# 4_MOTORES_DC.net
KiCad netlist of a schematic drawn in Altium Designer
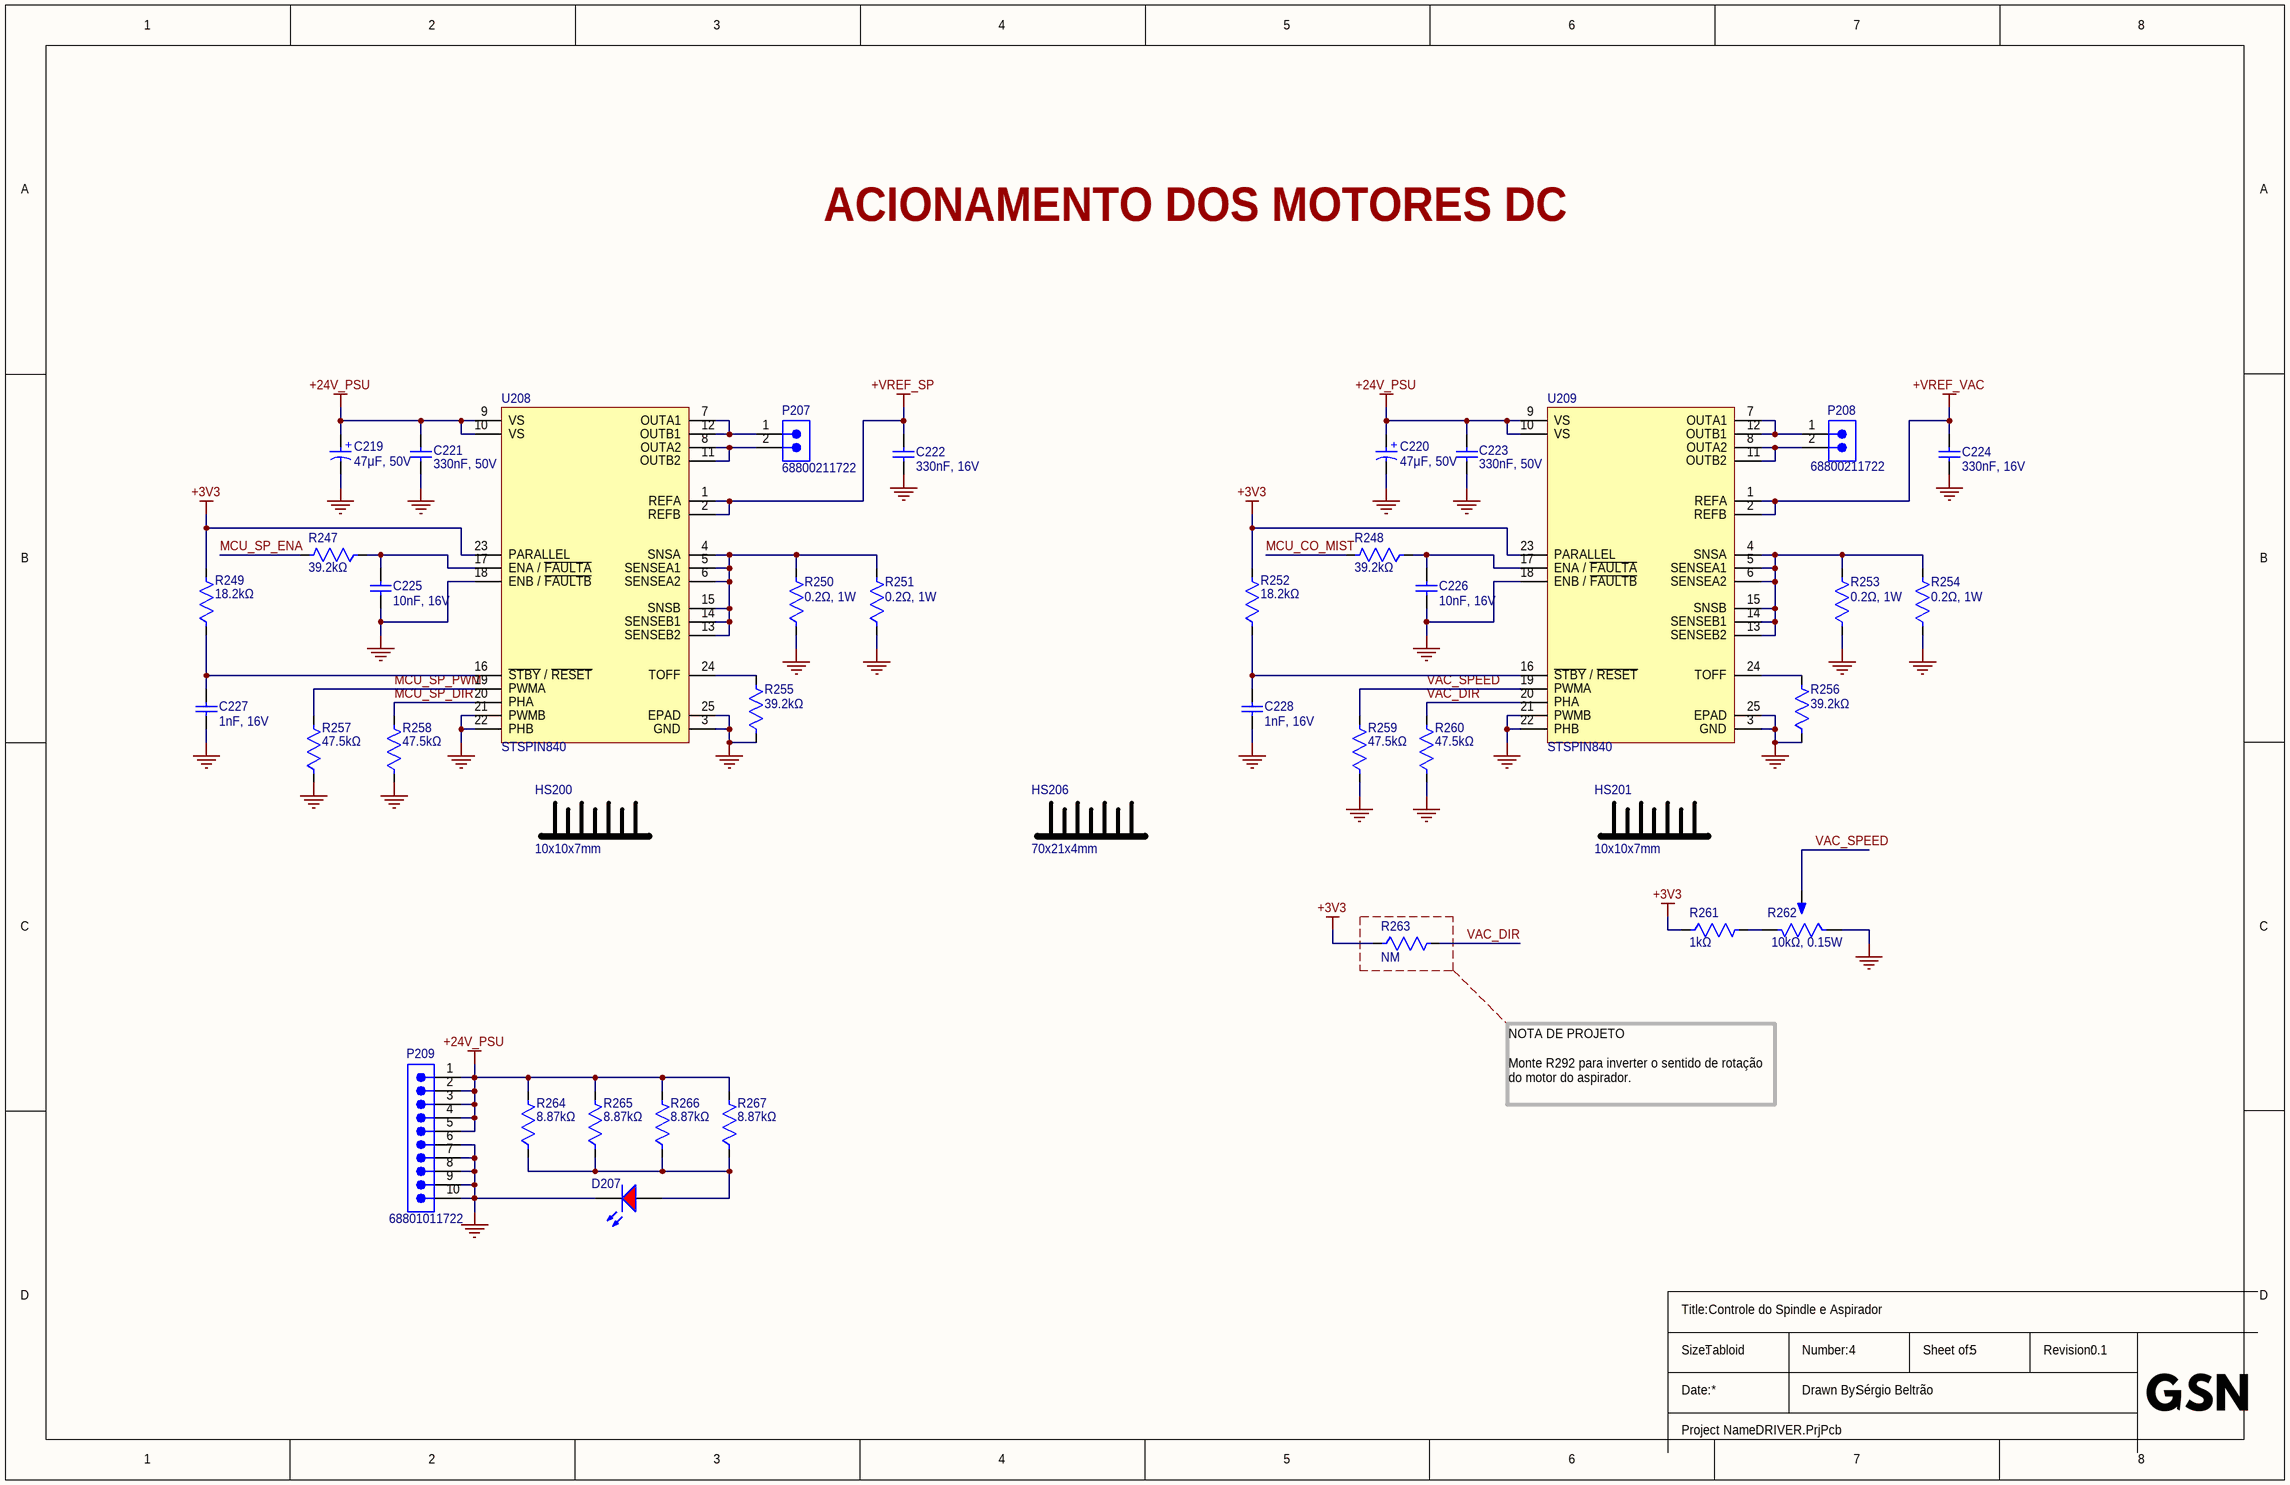
[diagram p0: 4_MOTORES_DC.SchDoc]

(export (version "E")
  (design (tool "Eeschema 10.0.6"))
  (components
    (comp (ref "C219")
      (value "47μF, 50V")
      (footprint "WCAP-ASLI_D6.3H7.7")
      (description "WCAP-ASLI Aluminum Electrolytic Capacitor, V-Chip, SMT, 6.3mm x 7.7mm, 47μF, 50V")
      (fields
        (field (name "MANUFACTURER PART NUMBER") "865080645012")
        (field (name "MANUFACTURER") "Wurth Elektronik")
      )
      (libsource (lib "WE - Passive Components") (part "Capacitor_Polarized"))
    )
    (comp (ref "C220")
      (value "47μF, 50V")
      (footprint "WCAP-ASLI_D6.3H7.7")
      (description "WCAP-ASLI Aluminum Electrolytic Capacitor, V-Chip, SMT, 6.3mm x 7.7mm, 47μF, 50V")
      (fields
        (field (name "MANUFACTURER PART NUMBER") "865080645012")
        (field (name "MANUFACTURER") "Wurth Elektronik")
      )
      (libsource (lib "WE - Passive Components") (part "Capacitor_Polarized"))
    )
    (comp (ref "C221")
      (value "330nF, 50V")
      (footprint "WCAP-CSGP_0603_L1.6W0.8H0.8_Wave")
      (description "WCAP-CSGP Multilayer Ceramic Chip Capacitor, General Purpose, size 0603, 330nF, 50V")
      (fields
        (field (name "MANUFACTURER PART NUMBER") "885012206121")
        (field (name "MANUFACTURER") "Wurth Elektronik")
      )
      (libsource (lib "WE - Passive Components") (part "Capacitor_Non-Polarized"))
    )
    (comp (ref "C222")
      (value "330nF, 16V")
      (footprint "WCAP-CSGP_0603_L1.6W0.8H0.8_Wave")
      (description "WCAP-CSGP Multilayer Ceramic Chip Capacitor, General Purpose, size 0603, 330nF, 16V")
      (fields
        (field (name "MANUFACTURER PART NUMBER") "885012206049")
        (field (name "MANUFACTURER") "Wurth Elektronik")
      )
      (libsource (lib "WE - Passive Components") (part "Capacitor_Non-Polarized"))
    )
    (comp (ref "C223")
      (value "330nF, 50V")
      (footprint "WCAP-CSGP_0603_L1.6W0.8H0.8_Wave")
      (description "WCAP-CSGP Multilayer Ceramic Chip Capacitor, General Purpose, size 0603, 330nF, 50V")
      (fields
        (field (name "MANUFACTURER PART NUMBER") "885012206121")
        (field (name "MANUFACTURER") "Wurth Elektronik")
      )
      (libsource (lib "WE - Passive Components") (part "Capacitor_Non-Polarized"))
    )
    (comp (ref "C224")
      (value "330nF, 16V")
      (footprint "WCAP-CSGP_0603_L1.6W0.8H0.8_Wave")
      (description "WCAP-CSGP Multilayer Ceramic Chip Capacitor, General Purpose, size 0603, 330nF, 16V")
      (fields
        (field (name "MANUFACTURER PART NUMBER") "885012206049")
        (field (name "MANUFACTURER") "Wurth Elektronik")
      )
      (libsource (lib "WE - Passive Components") (part "Capacitor_Non-Polarized"))
    )
    (comp (ref "C225")
      (value "10nF, 16V")
      (footprint "WCAP-CSGP_0603_L1.6W0.8H0.8_Wave")
      (description "WCAP-CSGP Multilayer Ceramic Chip Capacitor, General Purpose, size 0603, 10nF, 16V")
      (fields
        (field (name "MANUFACTURER PART NUMBER") "885012206040")
        (field (name "MANUFACTURER") "Wurth Elektronik")
      )
      (libsource (lib "WE - Passive Components") (part "Capacitor_Non-Polarized"))
    )
    (comp (ref "C226")
      (value "10nF, 16V")
      (footprint "WCAP-CSGP_0603_L1.6W0.8H0.8_Wave")
      (description "WCAP-CSGP Multilayer Ceramic Chip Capacitor, General Purpose, size 0603, 10nF, 16V")
      (fields
        (field (name "MANUFACTURER PART NUMBER") "885012206040")
        (field (name "MANUFACTURER") "Wurth Elektronik")
      )
      (libsource (lib "WE - Passive Components") (part "Capacitor_Non-Polarized"))
    )
    (comp (ref "C227")
      (value "1nF, 16V")
      (footprint "WCAP-CSGP_0603_L1.6W0.8H0.8_Wave")
      (description "WCAP-CSGP Multilayer Ceramic Chip Capacitor, General Purpose, size 0603, 1nF, 16V")
      (fields
        (field (name "MANUFACTURER PART NUMBER") "885012206034")
        (field (name "MANUFACTURER") "Wurth Elektronik")
      )
      (libsource (lib "WE - Passive Components") (part "Capacitor_Non-Polarized"))
    )
    (comp (ref "C228")
      (value "1nF, 16V")
      (footprint "WCAP-CSGP_0603_L1.6W0.8H0.8_Wave")
      (description "WCAP-CSGP Multilayer Ceramic Chip Capacitor, General Purpose, size 0603, 1nF, 16V")
      (fields
        (field (name "MANUFACTURER PART NUMBER") "885012206034")
        (field (name "MANUFACTURER") "Wurth Elektronik")
      )
      (libsource (lib "WE - Passive Components") (part "Capacitor_Non-Polarized"))
    )
    (comp (ref "D207")
      (value "Red, 2V, 140deg")
      (footprint "WL-SMCW_0603_150060xx75003")
      (description "WL-SMCW Mono-color Chip LED Waterclear, SMT, size 0603, Red, 2V, 140°")
      (fields
        (field (name "MANUFACTURER PART NUMBER") "150060RS75003")
        (field (name "MANUFACTURER") "Wurth Elektronik")
      )
      (libsource (lib "WE - Optoelectronic Components") (part "LED_Red_1A-2K"))
    )
    (comp (ref "HS200")
      (value "10x10x7mm")
      (footprint "HEATSINK_10MM_10MM_7MM")
      (description "GENERIC HEATSINK 10X10X7MM")
      (fields (field (name "MANUFACTURER") "OEM") (field (name "MANUFACTURER PART NUMBER") "None"))
      (libsource (lib "Electro-Mechanical") (part "GENERIC-HEATSINK-10X10X7MM"))
    )
    (comp (ref "HS201")
      (value "10x10x7mm")
      (footprint "HEATSINK_10MM_10MM_7MM")
      (description "GENERIC HEATSINK 10X10X7MM")
      (fields (field (name "MANUFACTURER") "OEM") (field (name "MANUFACTURER PART NUMBER") "None"))
      (libsource (lib "Electro-Mechanical") (part "GENERIC-HEATSINK-10X10X7MM"))
    )
    (comp (ref "HS206")
      (value "70x21x4mm")
      (footprint "HEATSINK_70MM_21MM_4MM")
      (description "GENERIC HEATSINK 70X21X4MM")
      (fields (field (name "MANUFACTURER") "OEM") (field (name "MANUFACTURER PART NUMBER") "None"))
      (libsource (lib "Electro-Mechanical") (part "GENERIC-HEATSINK-70X21X4MM"))
    )
    (comp (ref "P207")
      (value "68800211722")
      (footprint "68800211722")
      (description "WR-WTB “J” Type THT Male Horizontal Shrouded Header, pitch 2.5 mm, 2 pins")
      (fields (field (name "MANUFACTURER") "Wurth Elektronik"))
      (libsource (lib "WE - Electromechanical Components") (part "Header_Male_1R_02P"))
    )
    (comp (ref "P208")
      (value "68800211722")
      (footprint "68800211722")
      (description "WR-WTB “J” Type THT Male Horizontal Shrouded Header, pitch 2.5 mm, 2 pins")
      (fields (field (name "MANUFACTURER") "Wurth Elektronik"))
      (libsource (lib "WE - Electromechanical Components") (part "Header_Male_1R_02P"))
    )
    (comp (ref "P209")
      (value "68801011722")
      (footprint "68801011722")
      (description "WR-WTB “J” Type THT Male Horizontal Shrouded Header, pitch 2.5 mm, 10 pins")
      (fields (field (name "MANUFACTURER") "Wurth Elektronik"))
      (libsource (lib "WE - Electromechanical Components") (part "Header_Male_1R_10P"))
    )
    (comp (ref "R247")
      (value "39.2kΩ")
      (footprint "0603-WAVE")
      (description "RES 39.2K OHM 1% 1/10W 0603")
      (fields
        (field (name "MANUFACTURER PART NUMBER") "RC0603FR-0739K2L")
        (field (name "MANUFACTURER") "Yageo Group")
      )
      (libsource (lib "Resistors-0603-E96-Yageo") (part "RC0603FR-0739K2L"))
    )
    (comp (ref "R248")
      (value "39.2kΩ")
      (footprint "0603-WAVE")
      (description "RES 39.2K OHM 1% 1/10W 0603")
      (fields
        (field (name "MANUFACTURER PART NUMBER") "RC0603FR-0739K2L")
        (field (name "MANUFACTURER") "Yageo Group")
      )
      (libsource (lib "Resistors-0603-E96-Yageo") (part "RC0603FR-0739K2L"))
    )
    (comp (ref "R249")
      (value "18.2kΩ")
      (footprint "0603-WAVE")
      (description "RES 18.2K OHM 1% 1/10W 0603")
      (fields
        (field (name "MANUFACTURER PART NUMBER") "RC0603FR-0718K2L")
        (field (name "MANUFACTURER") "Yageo Group")
      )
      (libsource (lib "Resistors-0603-E96-Yageo") (part "RC0603FR-0718K2L"))
    )
    (comp (ref "R250")
      (value "0.2Ω, 1W")
      (footprint "2512-WAVE")
      (description "RES 0.2 OHM 1% 1W 2512")
      (fields
        (field (name "MANUFACTURER") "Yageo Group")
        (field (name "MANUFACTURER PART NUMBER") "RL2512FK-070R2L")
      )
      (libsource (lib "Resistors-2512-Shunt") (part "RL2512FK-070R2L"))
    )
    (comp (ref "R251")
      (value "0.2Ω, 1W")
      (footprint "2512-WAVE")
      (description "RES 0.2 OHM 1% 1W 2512")
      (fields
        (field (name "MANUFACTURER") "Yageo Group")
        (field (name "MANUFACTURER PART NUMBER") "RL2512FK-070R2L")
      )
      (libsource (lib "Resistors-2512-Shunt") (part "RL2512FK-070R2L"))
    )
    (comp (ref "R252")
      (value "18.2kΩ")
      (footprint "0603-WAVE")
      (description "RES 18.2K OHM 1% 1/10W 0603")
      (fields
        (field (name "MANUFACTURER PART NUMBER") "RC0603FR-0718K2L")
        (field (name "MANUFACTURER") "Yageo Group")
      )
      (libsource (lib "Resistors-0603-E96-Yageo") (part "RC0603FR-0718K2L"))
    )
    (comp (ref "R253")
      (value "0.2Ω, 1W")
      (footprint "2512-WAVE")
      (description "RES 0.2 OHM 1% 1W 2512")
      (fields
        (field (name "MANUFACTURER") "Yageo Group")
        (field (name "MANUFACTURER PART NUMBER") "RL2512FK-070R2L")
      )
      (libsource (lib "Resistors-2512-Shunt") (part "RL2512FK-070R2L"))
    )
    (comp (ref "R254")
      (value "0.2Ω, 1W")
      (footprint "2512-WAVE")
      (description "RES 0.2 OHM 1% 1W 2512")
      (fields
        (field (name "MANUFACTURER") "Yageo Group")
        (field (name "MANUFACTURER PART NUMBER") "RL2512FK-070R2L")
      )
      (libsource (lib "Resistors-2512-Shunt") (part "RL2512FK-070R2L"))
    )
    (comp (ref "R255")
      (value "39.2kΩ")
      (footprint "0603-WAVE")
      (description "RES 39.2K OHM 1% 1/10W 0603")
      (fields
        (field (name "MANUFACTURER PART NUMBER") "RC0603FR-0739K2L")
        (field (name "MANUFACTURER") "Yageo Group")
      )
      (libsource (lib "Resistors-0603-E96-Yageo") (part "RC0603FR-0739K2L"))
    )
    (comp (ref "R256")
      (value "39.2kΩ")
      (footprint "0603-WAVE")
      (description "RES 39.2K OHM 1% 1/10W 0603")
      (fields
        (field (name "MANUFACTURER PART NUMBER") "RC0603FR-0739K2L")
        (field (name "MANUFACTURER") "Yageo Group")
      )
      (libsource (lib "Resistors-0603-E96-Yageo") (part "RC0603FR-0739K2L"))
    )
    (comp (ref "R257")
      (value "47.5kΩ")
      (footprint "0603-WAVE")
      (description "RES 47.5K OHM 1% 1/10W 0603")
      (fields
        (field (name "MANUFACTURER PART NUMBER") "RC0603FR-0747K5L")
        (field (name "MANUFACTURER") "Yageo Group")
      )
      (libsource (lib "Resistors-0603-E96-Yageo") (part "RC0603FR-0747K5L"))
    )
    (comp (ref "R258")
      (value "47.5kΩ")
      (footprint "0603-WAVE")
      (description "RES 47.5K OHM 1% 1/10W 0603")
      (fields
        (field (name "MANUFACTURER PART NUMBER") "RC0603FR-0747K5L")
        (field (name "MANUFACTURER") "Yageo Group")
      )
      (libsource (lib "Resistors-0603-E96-Yageo") (part "RC0603FR-0747K5L"))
    )
    (comp (ref "R259")
      (value "47.5kΩ")
      (footprint "0603-WAVE")
      (description "RES 47.5K OHM 1% 1/10W 0603")
      (fields
        (field (name "MANUFACTURER PART NUMBER") "RC0603FR-0747K5L")
        (field (name "MANUFACTURER") "Yageo Group")
      )
      (libsource (lib "Resistors-0603-E96-Yageo") (part "RC0603FR-0747K5L"))
    )
    (comp (ref "R260")
      (value "47.5kΩ")
      (footprint "0603-WAVE")
      (description "RES 47.5K OHM 1% 1/10W 0603")
      (fields
        (field (name "MANUFACTURER PART NUMBER") "RC0603FR-0747K5L")
        (field (name "MANUFACTURER") "Yageo Group")
      )
      (libsource (lib "Resistors-0603-E96-Yageo") (part "RC0603FR-0747K5L"))
    )
    (comp (ref "R261")
      (value "1kΩ")
      (footprint "0603-WAVE")
      (description "RES 1K OHM 1% 1/10W 0603")
      (fields
        (field (name "MANUFACTURER PART NUMBER") "RC0603FR-071KL")
        (field (name "MANUFACTURER") "Yageo Group")
      )
      (libsource (lib "Resistors-0603-E96-Yageo") (part "RC0603FR-071KL"))
    )
    (comp (ref "R262")
      (value "10kΩ, 0.15W")
      (footprint "TRIM-3P80MM_3P60MM")
      (description "TRIMMER 10K OHM 0.15W J LEAD TOP")
      (fields (field (name "MANUFACTURER") "Bourns") (field (name "MANUFACTURER PART NUMBER") "TC33X-2-103E"))
      (libsource (lib "Potentiometers") (part "TC33X-2-103E"))
    )
    (comp (ref "R263")
      (value "NM")
      (footprint "0603-WAVE")
      (description "RES 0 OHM 1% 1/10W 0603")
      (fields
        (field (name "MANUFACTURER PART NUMBER") "RC0603FR-070RL")
        (field (name "MANUFACTURER") "Yageo Group")
      )
      (libsource (lib "Resistors-0603-E96-Yageo") (part "RC0603FR-070RL"))
    )
    (comp (ref "R264")
      (value "8.87kΩ")
      (footprint "0805-WAVE")
      (description "RES 8.87K OHM 1% 1/8W 0805")
      (fields
        (field (name "MANUFACTURER") "Yageo Group")
        (field (name "MANUFACTURER PART NUMBER") "RC0805FR-078K87L")
      )
      (libsource (lib "Resistors-0805-E96-Yageo") (part "RC0805FR-078K87L"))
    )
    (comp (ref "R265")
      (value "8.87kΩ")
      (footprint "0805-WAVE")
      (description "RES 8.87K OHM 1% 1/8W 0805")
      (fields
        (field (name "MANUFACTURER") "Yageo Group")
        (field (name "MANUFACTURER PART NUMBER") "RC0805FR-078K87L")
      )
      (libsource (lib "Resistors-0805-E96-Yageo") (part "RC0805FR-078K87L"))
    )
    (comp (ref "R266")
      (value "8.87kΩ")
      (footprint "0805-WAVE")
      (description "RES 8.87K OHM 1% 1/8W 0805")
      (fields
        (field (name "MANUFACTURER") "Yageo Group")
        (field (name "MANUFACTURER PART NUMBER") "RC0805FR-078K87L")
      )
      (libsource (lib "Resistors-0805-E96-Yageo") (part "RC0805FR-078K87L"))
    )
    (comp (ref "R267")
      (value "8.87kΩ")
      (footprint "0805-WAVE")
      (description "RES 8.87K OHM 1% 1/8W 0805")
      (fields
        (field (name "MANUFACTURER") "Yageo Group")
        (field (name "MANUFACTURER PART NUMBER") "RC0805FR-078K87L")
      )
      (libsource (lib "Resistors-0805-E96-Yageo") (part "RC0805FR-078K87L"))
    )
    (comp (ref "U208")
      (value "STSPIN840")
      (footprint "24-TQFPN")
      (description "IC MOTOR DRIVER 7V-45V 24TQFPN")
      (fields (field (name "MANUFACTURER") "STMicroelectronics"))
      (libsource (lib "Motor-Drivers") (part "STSPIN840"))
    )
    (comp (ref "U209")
      (value "STSPIN840")
      (footprint "24-TQFPN")
      (description "IC MOTOR DRIVER 7V-45V 24TQFPN")
      (fields (field (name "MANUFACTURER") "STMicroelectronics"))
      (libsource (lib "Motor-Drivers") (part "STSPIN840"))
    )
  )
  (nets
    (net (code "1") (name "+3V3") (class "Default")
      (node (ref "R249") (pin "2") (pinfunction "2_2") (pintype "passive"))
      (node (ref "R252") (pin "2") (pinfunction "2_2") (pintype "passive"))
      (node (ref "R261") (pin "1") (pinfunction "1_1") (pintype "passive"))
      (node (ref "R263") (pin "1") (pinfunction "1_1") (pintype "passive"))
      (node (ref "U208") (pin "23") (pinfunction "PARALLEL_23") (pintype "passive"))
      (node (ref "U209") (pin "23") (pinfunction "PARALLEL_23") (pintype "passive"))
    )
    (net (code "2") (name "+24V_PSU") (class "Default")
      (node (ref "C219") (pin "1") (pinfunction "P_1") (pintype "passive"))
      (node (ref "C220") (pin "1") (pinfunction "P_1") (pintype "passive"))
      (node (ref "C221") (pin "2") (pinfunction "2_2") (pintype "passive"))
      (node (ref "C223") (pin "2") (pinfunction "2_2") (pintype "passive"))
      (node (ref "P209") (pin "1") (pinfunction "1_1") (pintype "passive"))
      (node (ref "P209") (pin "2") (pinfunction "2_2") (pintype "passive"))
      (node (ref "P209") (pin "3") (pinfunction "3_3") (pintype "passive"))
      (node (ref "P209") (pin "4") (pinfunction "4_4") (pintype "passive"))
      (node (ref "P209") (pin "5") (pinfunction "5_5") (pintype "passive"))
      (node (ref "R264") (pin "2") (pinfunction "2_2") (pintype "passive"))
      (node (ref "R265") (pin "2") (pinfunction "2_2") (pintype "passive"))
      (node (ref "R266") (pin "2") (pinfunction "2_2") (pintype "passive"))
      (node (ref "R267") (pin "2") (pinfunction "2_2") (pintype "passive"))
      (node (ref "U208") (pin "10") (pinfunction "VS_10") (pintype "passive"))
      (node (ref "U208") (pin "9") (pinfunction "VS_9") (pintype "passive"))
      (node (ref "U209") (pin "10") (pinfunction "VS_10") (pintype "passive"))
      (node (ref "U209") (pin "9") (pinfunction "VS_9") (pintype "passive"))
    )
    (net (code "3") (name "+VREF_SP") (class "Default")
      (node (ref "C222") (pin "2") (pinfunction "2_2") (pintype "passive"))
      (node (ref "U208") (pin "1") (pinfunction "REFA_1") (pintype "passive"))
      (node (ref "U208") (pin "2") (pinfunction "REFB_2") (pintype "passive"))
    )
    (net (code "4") (name "+VREF_VAC") (class "Default")
      (node (ref "C224") (pin "2") (pinfunction "2_2") (pintype "passive"))
      (node (ref "U209") (pin "1") (pinfunction "REFA_1") (pintype "passive"))
      (node (ref "U209") (pin "2") (pinfunction "REFB_2") (pintype "passive"))
    )
    (net (code "5") (name "/MCU_CO_MIST") (class "Default")
      (node (ref "R248") (pin "2") (pinfunction "2_2") (pintype "passive"))
    )
    (net (code "6") (name "/MCU_SP_DIR") (class "Default")
      (node (ref "R258") (pin "2") (pinfunction "2_2") (pintype "passive"))
      (node (ref "U208") (pin "20") (pinfunction "PHA_20") (pintype "passive"))
    )
    (net (code "7") (name "/MCU_SP_ENA") (class "Default")
      (node (ref "R247") (pin "2") (pinfunction "2_2") (pintype "passive"))
    )
    (net (code "8") (name "/MCU_SP_PWM") (class "Default")
      (node (ref "R257") (pin "2") (pinfunction "2_2") (pintype "passive"))
      (node (ref "U208") (pin "19") (pinfunction "PWMA_19") (pintype "passive"))
    )
    (net (code "9") (name "/VAC_DIR") (class "Default")
      (node (ref "R260") (pin "2") (pinfunction "2_2") (pintype "passive"))
      (node (ref "R263") (pin "2") (pinfunction "2_2") (pintype "passive"))
      (node (ref "U209") (pin "20") (pinfunction "PHA_20") (pintype "passive"))
    )
    (net (code "10") (name "/VAC_SPEED") (class "Default")
      (node (ref "R259") (pin "2") (pinfunction "2_2") (pintype "passive"))
      (node (ref "R262") (pin "2") (pinfunction "WIPER_2") (pintype "passive"))
      (node (ref "U209") (pin "19") (pinfunction "PWMA_19") (pintype "passive"))
    )
    (net (code "11") (name "GND") (class "Default")
      (node (ref "C219") (pin "2") (pinfunction "N_2") (pintype "passive"))
      (node (ref "C220") (pin "2") (pinfunction "N_2") (pintype "passive"))
      (node (ref "C221") (pin "1") (pinfunction "1_1") (pintype "passive"))
      (node (ref "C222") (pin "1") (pinfunction "1_1") (pintype "passive"))
      (node (ref "C223") (pin "1") (pinfunction "1_1") (pintype "passive"))
      (node (ref "C224") (pin "1") (pinfunction "1_1") (pintype "passive"))
      (node (ref "C225") (pin "1") (pinfunction "1_1") (pintype "passive"))
      (node (ref "C226") (pin "1") (pinfunction "1_1") (pintype "passive"))
      (node (ref "C227") (pin "1") (pinfunction "1_1") (pintype "passive"))
      (node (ref "C228") (pin "1") (pinfunction "1_1") (pintype "passive"))
      (node (ref "D207") (pin "2") (pinfunction "K_2") (pintype "passive"))
      (node (ref "P209") (pin "10") (pinfunction "10_10") (pintype "passive"))
      (node (ref "P209") (pin "6") (pinfunction "6_6") (pintype "passive"))
      (node (ref "P209") (pin "7") (pinfunction "7_7") (pintype "passive"))
      (node (ref "P209") (pin "8") (pinfunction "8_8") (pintype "passive"))
      (node (ref "P209") (pin "9") (pinfunction "9_9") (pintype "passive"))
      (node (ref "R250") (pin "1") (pinfunction "1_1") (pintype "passive"))
      (node (ref "R251") (pin "1") (pinfunction "1_1") (pintype "passive"))
      (node (ref "R253") (pin "1") (pinfunction "1_1") (pintype "passive"))
      (node (ref "R254") (pin "1") (pinfunction "1_1") (pintype "passive"))
      (node (ref "R255") (pin "1") (pinfunction "1_1") (pintype "passive"))
      (node (ref "R256") (pin "1") (pinfunction "1_1") (pintype "passive"))
      (node (ref "R257") (pin "1") (pinfunction "1_1") (pintype "passive"))
      (node (ref "R258") (pin "1") (pinfunction "1_1") (pintype "passive"))
      (node (ref "R259") (pin "1") (pinfunction "1_1") (pintype "passive"))
      (node (ref "R260") (pin "1") (pinfunction "1_1") (pintype "passive"))
      (node (ref "R262") (pin "1") (pinfunction "CCW_1") (pintype "passive"))
      (node (ref "U208") (pin "18") (pinfunction "ENB_/_~{FAULTB}_18") (pintype "passive"))
      (node (ref "U208") (pin "21") (pinfunction "PWMB_21") (pintype "passive"))
      (node (ref "U208") (pin "22") (pinfunction "PHB_22") (pintype "passive"))
      (node (ref "U208") (pin "25") (pinfunction "EPAD_25") (pintype "passive"))
      (node (ref "U208") (pin "3") (pinfunction "GND_3") (pintype "passive"))
      (node (ref "U209") (pin "18") (pinfunction "ENB_/_~{FAULTB}_18") (pintype "passive"))
      (node (ref "U209") (pin "21") (pinfunction "PWMB_21") (pintype "passive"))
      (node (ref "U209") (pin "22") (pinfunction "PHB_22") (pintype "passive"))
      (node (ref "U209") (pin "25") (pinfunction "EPAD_25") (pintype "passive"))
      (node (ref "U209") (pin "3") (pinfunction "GND_3") (pintype "passive"))
    )
    (net (code "12") (name "Net-(D207-A)") (class "Default")
      (node (ref "D207") (pin "1") (pinfunction "A_1") (pintype "passive"))
      (node (ref "R264") (pin "1") (pinfunction "1_1") (pintype "passive"))
      (node (ref "R265") (pin "1") (pinfunction "1_1") (pintype "passive"))
      (node (ref "R266") (pin "1") (pinfunction "1_1") (pintype "passive"))
      (node (ref "R267") (pin "1") (pinfunction "1_1") (pintype "passive"))
    )
    (net (code "13") (name "Net-(R262-CW)") (class "Default")
      (node (ref "R261") (pin "2") (pinfunction "2_2") (pintype "passive"))
      (node (ref "R262") (pin "3") (pinfunction "CW_3") (pintype "passive"))
    )
    (net (code "14") (name "Net-(U208-ENA_{slash}_~{FAULTA})") (class "Default")
      (node (ref "C225") (pin "2") (pinfunction "2_2") (pintype "passive"))
      (node (ref "R247") (pin "1") (pinfunction "1_1") (pintype "passive"))
      (node (ref "U208") (pin "17") (pinfunction "ENA_/_~{FAULTA}_17") (pintype "passive"))
    )
    (net (code "15") (name "Net-(U208-OUTA1)") (class "Default")
      (node (ref "P207") (pin "1") (pinfunction "1_1") (pintype "passive"))
      (node (ref "U208") (pin "12") (pinfunction "OUTB1_12") (pintype "passive"))
      (node (ref "U208") (pin "7") (pinfunction "OUTA1_7") (pintype "passive"))
    )
    (net (code "16") (name "Net-(U208-OUTA2)") (class "Default")
      (node (ref "P207") (pin "2") (pinfunction "2_2") (pintype "passive"))
      (node (ref "U208") (pin "11") (pinfunction "OUTB2_11") (pintype "passive"))
      (node (ref "U208") (pin "8") (pinfunction "OUTA2_8") (pintype "passive"))
    )
    (net (code "17") (name "Net-(U208-SENSEA1)") (class "Default")
      (node (ref "R250") (pin "2") (pinfunction "2_2") (pintype "passive"))
      (node (ref "R251") (pin "2") (pinfunction "2_2") (pintype "passive"))
      (node (ref "U208") (pin "13") (pinfunction "SENSEB2_13") (pintype "passive"))
      (node (ref "U208") (pin "14") (pinfunction "SENSEB1_14") (pintype "passive"))
      (node (ref "U208") (pin "15") (pinfunction "SNSB_15") (pintype "passive"))
      (node (ref "U208") (pin "4") (pinfunction "SNSA_4") (pintype "passive"))
      (node (ref "U208") (pin "5") (pinfunction "SENSEA1_5") (pintype "passive"))
      (node (ref "U208") (pin "6") (pinfunction "SENSEA2_6") (pintype "passive"))
    )
    (net (code "18") (name "Net-(U208-TOFF)") (class "Default")
      (node (ref "R255") (pin "2") (pinfunction "2_2") (pintype "passive"))
      (node (ref "U208") (pin "24") (pinfunction "TOFF_24") (pintype "passive"))
    )
    (net (code "19") (name "Net-(U208-~{STBY}_{slash}_~{RESET})") (class "Default")
      (node (ref "C227") (pin "2") (pinfunction "2_2") (pintype "passive"))
      (node (ref "R249") (pin "1") (pinfunction "1_1") (pintype "passive"))
      (node (ref "U208") (pin "16") (pinfunction "~{STBY}_/_~{RESET}_16") (pintype "passive"))
    )
    (net (code "20") (name "Net-(U209-ENA_{slash}_~{FAULTA})") (class "Default")
      (node (ref "C226") (pin "2") (pinfunction "2_2") (pintype "passive"))
      (node (ref "R248") (pin "1") (pinfunction "1_1") (pintype "passive"))
      (node (ref "U209") (pin "17") (pinfunction "ENA_/_~{FAULTA}_17") (pintype "passive"))
    )
    (net (code "21") (name "Net-(U209-OUTA1)") (class "Default")
      (node (ref "P208") (pin "1") (pinfunction "1_1") (pintype "passive"))
      (node (ref "U209") (pin "12") (pinfunction "OUTB1_12") (pintype "passive"))
      (node (ref "U209") (pin "7") (pinfunction "OUTA1_7") (pintype "passive"))
    )
    (net (code "22") (name "Net-(U209-OUTA2)") (class "Default")
      (node (ref "P208") (pin "2") (pinfunction "2_2") (pintype "passive"))
      (node (ref "U209") (pin "11") (pinfunction "OUTB2_11") (pintype "passive"))
      (node (ref "U209") (pin "8") (pinfunction "OUTA2_8") (pintype "passive"))
    )
    (net (code "23") (name "Net-(U209-SENSEA1)") (class "Default")
      (node (ref "R253") (pin "2") (pinfunction "2_2") (pintype "passive"))
      (node (ref "R254") (pin "2") (pinfunction "2_2") (pintype "passive"))
      (node (ref "U209") (pin "13") (pinfunction "SENSEB2_13") (pintype "passive"))
      (node (ref "U209") (pin "14") (pinfunction "SENSEB1_14") (pintype "passive"))
      (node (ref "U209") (pin "15") (pinfunction "SNSB_15") (pintype "passive"))
      (node (ref "U209") (pin "4") (pinfunction "SNSA_4") (pintype "passive"))
      (node (ref "U209") (pin "5") (pinfunction "SENSEA1_5") (pintype "passive"))
      (node (ref "U209") (pin "6") (pinfunction "SENSEA2_6") (pintype "passive"))
    )
    (net (code "24") (name "Net-(U209-TOFF)") (class "Default")
      (node (ref "R256") (pin "2") (pinfunction "2_2") (pintype "passive"))
      (node (ref "U209") (pin "24") (pinfunction "TOFF_24") (pintype "passive"))
    )
    (net (code "25") (name "Net-(U209-~{STBY}_{slash}_~{RESET})") (class "Default")
      (node (ref "C228") (pin "2") (pinfunction "2_2") (pintype "passive"))
      (node (ref "R252") (pin "1") (pinfunction "1_1") (pintype "passive"))
      (node (ref "U209") (pin "16") (pinfunction "~{STBY}_/_~{RESET}_16") (pintype "passive"))
    )
  )
)
